# ASBB_ADC.net
KiCad netlist of a schematic drawn in Altium Designer
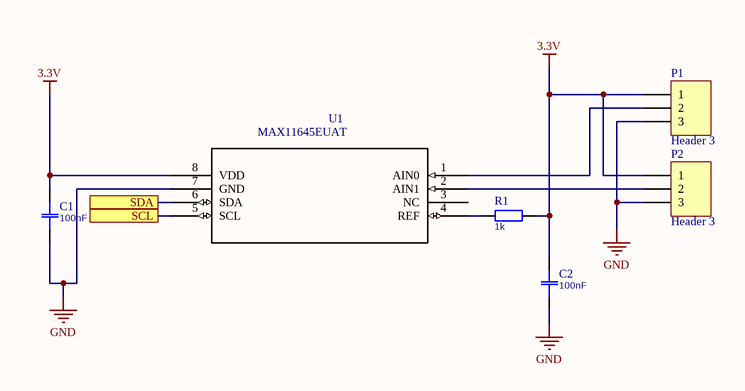
[diagram p0: ASBB_ADC.SchDoc]

(export (version "E")
  (design (tool "Eeschema 10.0.6"))
  (components
    (comp (ref "C1")
      (value "100nF")
      (footprint "0603")
      (description "Capacitor")
      (fields (field (name "PARTNUMBER") "?"))
      (libsource (lib "FZI") (part "Capacitor"))
    )
    (comp (ref "C2")
      (value "100nF")
      (footprint "0603")
      (description "Capacitor")
      (fields (field (name "PARTNUMBER") "?"))
      (libsource (lib "FZI") (part "Capacitor"))
    )
    (comp (ref "P1")
      (value "Header 3")
      (footprint "HDR1X3")
      (description "Header, 3-Pin")
      (fields (field (name "PUBLISHER") "Altium Limited"))
      (libsource (lib "Miscellaneous Connectors") (part "Header 3"))
    )
    (comp (ref "P2")
      (value "Header 3")
      (footprint "HDR1X3")
      (description "Header, 3-Pin")
      (fields (field (name "PUBLISHER") "Altium Limited"))
      (libsource (lib "Miscellaneous Connectors") (part "Header 3"))
    )
    (comp (ref "R1")
      (value "1k")
      (footprint "0603")
      (description "Resistor")
      (fields (field (name "PARTNUMBER") "?"))
      (libsource (lib "FZI") (part "Resistor"))
    )
    (comp (ref "U1")
      (value "MAX11645EUAT")
      (footprint "21-0036K")
      (description "Data acquisition IC - AD converter _ADC_ Maxim Integrated MAX11645EUA+ External , Internal uMAX 8")
      (fields (field (name "MF") "Maxim Integrated") (field (name "DIGI-KEY_PART_NUMBER") "MAX11645EUA+-ND"))
      (libsource (lib "MAX11645EUAT") (part "MAX11645EUAT"))
    )
  )
  (nets
    (net (code "1") (name "/SCL") (class "Default")
      (node (ref "U1") (pin "5") (pinfunction "SCL_5") (pintype "bidirectional"))
    )
    (net (code "2") (name "/SDA") (class "Default")
      (node (ref "U1") (pin "6") (pinfunction "SDA_6") (pintype "bidirectional"))
    )
    (net (code "3") (name "3.3V") (class "Default")
      (node (ref "C1") (pin "1") (pinfunction "1_1") (pintype "passive"))
      (node (ref "C2") (pin "1") (pinfunction "1_1") (pintype "passive"))
      (node (ref "P1") (pin "1") (pinfunction "1_1") (pintype "passive"))
      (node (ref "P2") (pin "1") (pinfunction "1_1") (pintype "passive"))
      (node (ref "R1") (pin "1") (pinfunction "1_1") (pintype "passive"))
      (node (ref "U1") (pin "8") (pinfunction "VDD_8") (pintype "power_in"))
    )
    (net (code "4") (name "GND") (class "Default")
      (node (ref "C1") (pin "2") (pinfunction "2_2") (pintype "passive"))
      (node (ref "C2") (pin "2") (pinfunction "2_2") (pintype "passive"))
      (node (ref "P1") (pin "3") (pinfunction "3_3") (pintype "passive"))
      (node (ref "P2") (pin "3") (pinfunction "3_3") (pintype "passive"))
      (node (ref "U1") (pin "7") (pinfunction "GND_7") (pintype "power_in"))
    )
    (net (code "5") (name "Net-(U1-AIN0)") (class "Default")
      (node (ref "P1") (pin "2") (pinfunction "2_2") (pintype "passive"))
      (node (ref "U1") (pin "1") (pinfunction "AIN0_1") (pintype "input"))
    )
    (net (code "6") (name "Net-(U1-AIN1)") (class "Default")
      (node (ref "P2") (pin "2") (pinfunction "2_2") (pintype "passive"))
      (node (ref "U1") (pin "2") (pinfunction "AIN1_2") (pintype "input"))
    )
    (net (code "7") (name "Net-(U1-REF)") (class "Default")
      (node (ref "R1") (pin "2") (pinfunction "2_2") (pintype "passive"))
      (node (ref "U1") (pin "4") (pinfunction "REF_4") (pintype "bidirectional"))
    )
    (net (code "8") (name "unconnected-(U1-NC-Pad3)") (class "Default")
      (node (ref "U1") (pin "3") (pinfunction "NC_3") (pintype "passive"))
    )
  )
)
